# MCU.net
KiCad netlist of a schematic drawn in Altium Designer
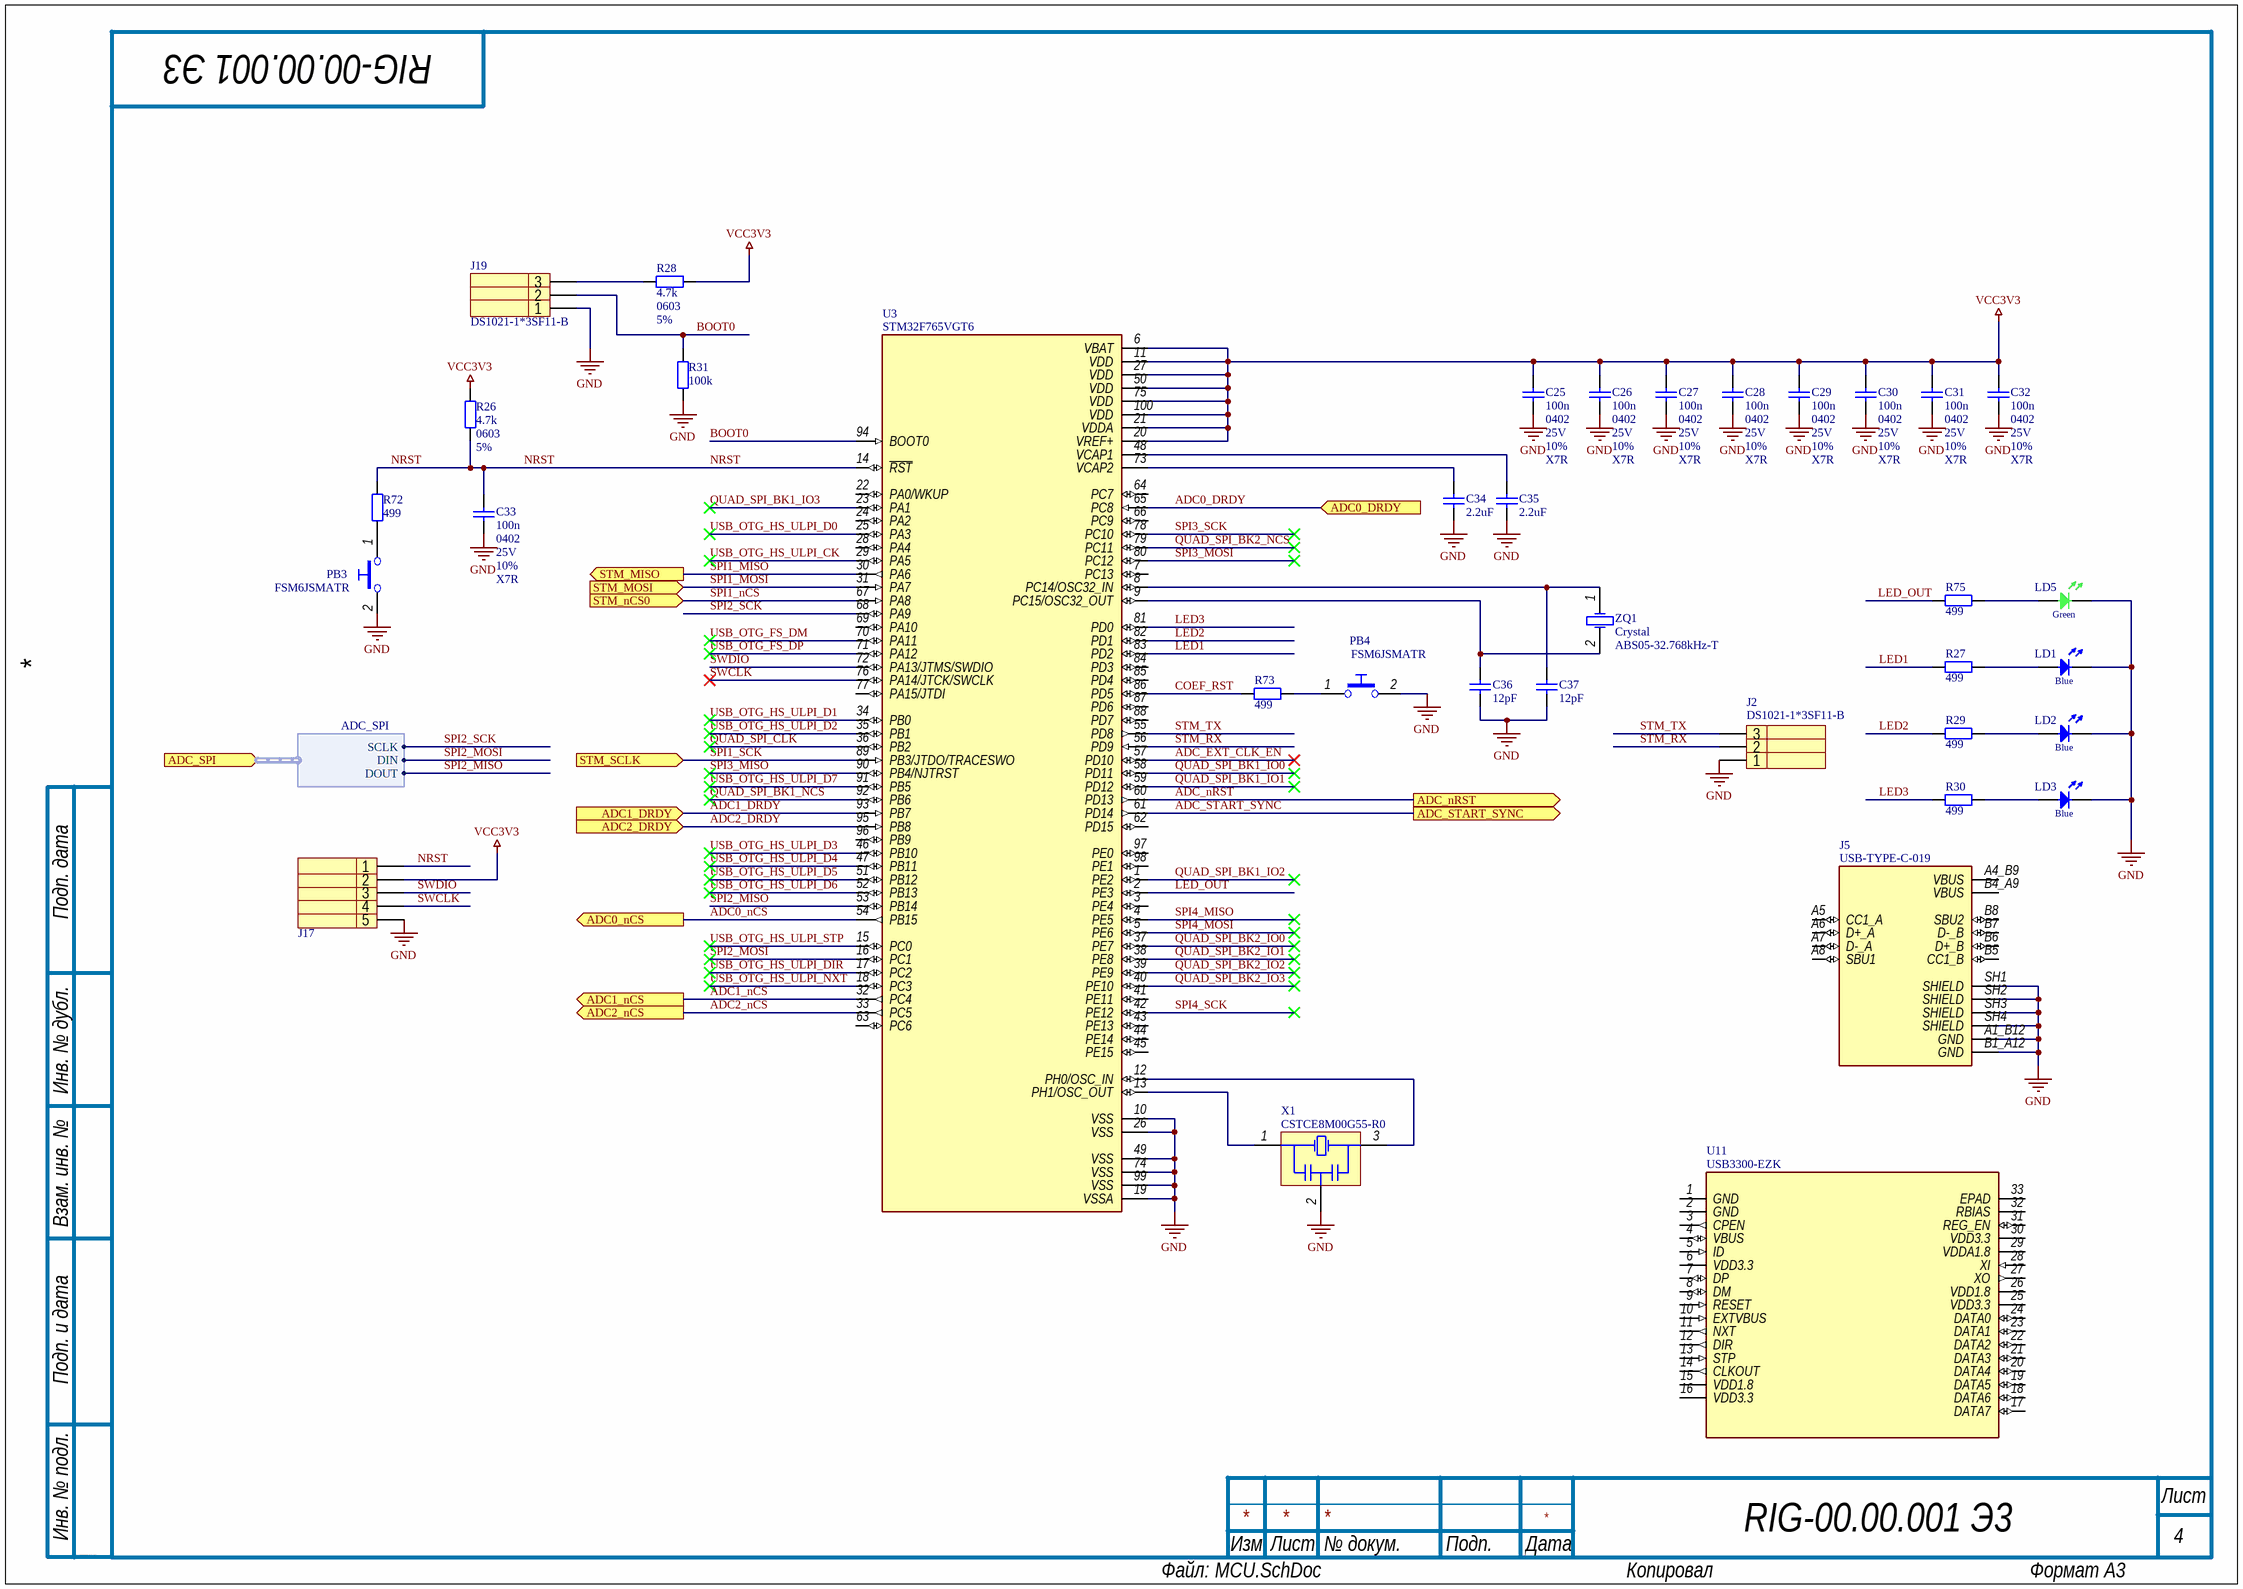
[diagram p0: MCU.SchDoc]

(export (version "E")
  (design (tool "Eeschema 10.0.6"))
  (components
    (comp (ref "C25")
      (value "100n")
      (footprint "CAPC1005X55N")
      (description "CAP CER 0402 100n 25V X7R")
      (fields
        (field (name "PART NUMBER") "GRM155R71E104KE14D")
        (field (name "DEVICE") "0402")
        (field (name "VOLTAGE") "25V")
        (field (name "TOLERANCE") "10%")
        (field (name "DIELECTRIC TYPE") "X7R")
        (field (name "MANUFACTURER") "Murata")
        (field (name "AUTHOR") "Krepak V.")
      )
      (libsource (lib "tgl_lib_altium") (part "Capacitor - non polarized"))
    )
    (comp (ref "C26")
      (value "100n")
      (footprint "CAPC1005X55N")
      (description "CAP CER 0402 100n 25V X7R")
      (fields
        (field (name "PART NUMBER") "GRM155R71E104KE14D")
        (field (name "DEVICE") "0402")
        (field (name "VOLTAGE") "25V")
        (field (name "TOLERANCE") "10%")
        (field (name "DIELECTRIC TYPE") "X7R")
        (field (name "MANUFACTURER") "Murata")
        (field (name "AUTHOR") "Krepak V.")
      )
      (libsource (lib "tgl_lib_altium") (part "Capacitor - non polarized"))
    )
    (comp (ref "C27")
      (value "100n")
      (footprint "CAPC1005X55N")
      (description "CAP CER 0402 100n 25V X7R")
      (fields
        (field (name "PART NUMBER") "GRM155R71E104KE14D")
        (field (name "DEVICE") "0402")
        (field (name "VOLTAGE") "25V")
        (field (name "TOLERANCE") "10%")
        (field (name "DIELECTRIC TYPE") "X7R")
        (field (name "MANUFACTURER") "Murata")
        (field (name "AUTHOR") "Krepak V.")
      )
      (libsource (lib "tgl_lib_altium") (part "Capacitor - non polarized"))
    )
    (comp (ref "C28")
      (value "100n")
      (footprint "CAPC1005X55N")
      (description "CAP CER 0402 100n 25V X7R")
      (fields
        (field (name "PART NUMBER") "GRM155R71E104KE14D")
        (field (name "DEVICE") "0402")
        (field (name "VOLTAGE") "25V")
        (field (name "TOLERANCE") "10%")
        (field (name "DIELECTRIC TYPE") "X7R")
        (field (name "MANUFACTURER") "Murata")
        (field (name "AUTHOR") "Krepak V.")
      )
      (libsource (lib "tgl_lib_altium") (part "Capacitor - non polarized"))
    )
    (comp (ref "C29")
      (value "100n")
      (footprint "CAPC1005X55N")
      (description "CAP CER 0402 100n 25V X7R")
      (fields
        (field (name "PART NUMBER") "GRM155R71E104KE14D")
        (field (name "DEVICE") "0402")
        (field (name "VOLTAGE") "25V")
        (field (name "TOLERANCE") "10%")
        (field (name "DIELECTRIC TYPE") "X7R")
        (field (name "MANUFACTURER") "Murata")
        (field (name "AUTHOR") "Krepak V.")
      )
      (libsource (lib "tgl_lib_altium") (part "Capacitor - non polarized"))
    )
    (comp (ref "C30")
      (value "100n")
      (footprint "CAPC1005X55N")
      (description "CAP CER 0402 100n 25V X7R")
      (fields
        (field (name "PART NUMBER") "GRM155R71E104KE14D")
        (field (name "DEVICE") "0402")
        (field (name "VOLTAGE") "25V")
        (field (name "TOLERANCE") "10%")
        (field (name "DIELECTRIC TYPE") "X7R")
        (field (name "MANUFACTURER") "Murata")
        (field (name "AUTHOR") "Krepak V.")
      )
      (libsource (lib "tgl_lib_altium") (part "Capacitor - non polarized"))
    )
    (comp (ref "C31")
      (value "100n")
      (footprint "CAPC1005X55N")
      (description "CAP CER 0402 100n 25V X7R")
      (fields
        (field (name "PART NUMBER") "GRM155R71E104KE14D")
        (field (name "DEVICE") "0402")
        (field (name "VOLTAGE") "25V")
        (field (name "TOLERANCE") "10%")
        (field (name "DIELECTRIC TYPE") "X7R")
        (field (name "MANUFACTURER") "Murata")
        (field (name "AUTHOR") "Krepak V.")
      )
      (libsource (lib "tgl_lib_altium") (part "Capacitor - non polarized"))
    )
    (comp (ref "C32")
      (value "100n")
      (footprint "CAPC1005X55N")
      (description "CAP CER 0402 100n 25V X7R")
      (fields
        (field (name "PART NUMBER") "GRM155R71E104KE14D")
        (field (name "DEVICE") "0402")
        (field (name "VOLTAGE") "25V")
        (field (name "TOLERANCE") "10%")
        (field (name "DIELECTRIC TYPE") "X7R")
        (field (name "MANUFACTURER") "Murata")
        (field (name "AUTHOR") "Krepak V.")
      )
      (libsource (lib "tgl_lib_altium") (part "Capacitor - non polarized"))
    )
    (comp (ref "C33")
      (value "100n")
      (footprint "CAPC1005X55N")
      (description "CAP CER 0402 100n 25V X7R")
      (fields
        (field (name "PART NUMBER") "GRM155R71E104KE14D")
        (field (name "DEVICE") "0402")
        (field (name "VOLTAGE") "25V")
        (field (name "TOLERANCE") "10%")
        (field (name "DIELECTRIC TYPE") "X7R")
        (field (name "MANUFACTURER") "Murata")
        (field (name "AUTHOR") "Krepak V.")
      )
      (libsource (lib "tgl_lib_altium") (part "Capacitor - non polarized"))
    )
    (comp (ref "C34")
      (value "2.2uF")
      (footprint "CAPC1005X55N")
      (description "CAP CER 0402 2.2uF 10V X5R")
      (fields
        (field (name "PART NUMBER") "GRM155R61A225KE95D")
        (field (name "VOLTAGE") "10V")
        (field (name "AUTHOR") "Krepak V.")
      )
      (libsource (lib "tgl_lib_altium") (part "Capacitor - non polarized"))
    )
    (comp (ref "C35")
      (value "2.2uF")
      (footprint "CAPC1005X55N")
      (description "CAP CER 0402 2.2uF 10V X5R")
      (fields
        (field (name "PART NUMBER") "GRM155R61A225KE95D")
        (field (name "VOLTAGE") "10V")
        (field (name "AUTHOR") "Krepak V.")
      )
      (libsource (lib "tgl_lib_altium") (part "Capacitor - non polarized"))
    )
    (comp (ref "C36")
      (value "12pF")
      (footprint "CAPC1005X55N")
      (description "CAP CER 0402 12pF 50V NP0")
      (fields
        (field (name "PART NUMBER") "GRM1555C1H120JA01D")
        (field (name "VOLTAGE") "50V")
        (field (name "AUTHOR") "Krepak V.")
      )
      (libsource (lib "tgl_lib_altium") (part "Capacitor - non polarized"))
    )
    (comp (ref "C37")
      (value "12pF")
      (footprint "CAPC1005X55N")
      (description "CAP CER 0402 12pF 50V NP0")
      (fields
        (field (name "PART NUMBER") "GRM1555C1H120JA01D")
        (field (name "VOLTAGE") "50V")
        (field (name "AUTHOR") "Krepak V.")
      )
      (libsource (lib "tgl_lib_altium") (part "Capacitor - non polarized"))
    )
    (comp (ref "J2")
      (value "DS1021-1*3SF11-B")
      (footprint "PLS-3")
      (fields (field (name "MANUFACTURER") "CONNFLY") (field (name "AUTHOR") "Arshanitsa D."))
      (libsource (lib "") (part "PLS-3_1"))
    )
    (comp (ref "J5")
      (value "USB-TYPE-C-019")
      (footprint "AMPHENOL_12402012E212A")
      (description "1 16P -25℃~+85℃ Type-C SMD USB, DVI, HDMI Connector Assemblies RoHS")
      (fields (field (name "MP") "12402012E212A") (field (name "MF") "Amphenol ICC (Commercial Products)"))
      (libsource (lib "tgl_lib_altium") (part "12402012E212A"))
    )
    (comp (ref "J17")
      (value "DS1021-1*5SF11-B")
      (footprint "PLS-5")
      (fields (field (name "MANUFACTURER") "CONNFLY") (field (name "AUTHOR") "Arshanitsa D."))
      (libsource (lib "tgl_lib_altium") (part "PLS-5"))
    )
    (comp (ref "J19")
      (value "DS1021-1*3SF11-B")
      (footprint "PLS-3")
      (fields (field (name "MANUFACTURER") "CONNFLY") (field (name "AUTHOR") "Arshanitsa D."))
      (libsource (lib "tgl_lib_altium") (part "PLS-3"))
    )
    (comp (ref "LD1")
      (value "Blue")
      (footprint "0603(LED_B)")
      (description "DIODE LTST-C191TBKT-5A")
      (fields (field (name "PART NUMBER") "LTST-C191TBKT-5A") (field (name "AUTHOR") "Krepak V."))
      (libsource (lib "tgl_lib_altium") (part "LED Blue 1A 2C"))
    )
    (comp (ref "LD2")
      (value "Blue")
      (footprint "0603(LED_B)")
      (description "DIODE LTST-C191TBKT-5A")
      (fields (field (name "PART NUMBER") "LTST-C191TBKT-5A") (field (name "AUTHOR") "Krepak V."))
      (libsource (lib "tgl_lib_altium") (part "LED Blue 1A 2C"))
    )
    (comp (ref "LD3")
      (value "Blue")
      (footprint "0603(LED_B)")
      (description "DIODE LTST-C191TBKT-5A")
      (fields (field (name "PART NUMBER") "LTST-C191TBKT-5A") (field (name "AUTHOR") "Krepak V."))
      (libsource (lib "tgl_lib_altium") (part "LED Blue 1A 2C"))
    )
    (comp (ref "LD5")
      (value "Green")
      (footprint "LD-3mm-G")
      (description "DIODE GREEN")
      (fields
        (field (name "PART NUMBER") "GNL-3012GD")
        (field (name "MANUFACTURER") "G-NOR OPTOELECTRONICS")
        (field (name "AUTHOR") "Krepak V.")
      )
      (libsource (lib "tgl_lib_altium") (part "LED Green 1A 2C"))
    )
    (comp (ref "PB3")
      (value "FSM6JSMATR")
      (footprint "FSMxJSMA-Series")
      (description "Tactile Switch SPST-NO Top Actuated Surface Mount")
      (fields (field (name "MANUFACTURER") "Te Connectivity") (field (name "AUTHOR") "Krepak V."))
      (libsource (lib "") (part "PB SPST 12NO_1"))
    )
    (comp (ref "PB4")
      (value "FSM6JSMATR")
      (footprint "FSMxJSMA-Series")
      (description "Tactile Switch SPST-NO Top Actuated Surface Mount")
      (fields (field (name "MANUFACTURER") "Te Connectivity") (field (name "AUTHOR") "Krepak V."))
      (libsource (lib "tgl_lib_altium") (part "PB SPST 12NO"))
    )
    (comp (ref "R26")
      (value "4.7k")
      (footprint "RESC1608X50N")
      (description "RES 0603 4.7k 5%")
      (fields
        (field (name "PART NUMBER") "RC0603JR-074K7L")
        (field (name "DEVICE") "0603")
        (field (name "TOLERANCE") "5%")
        (field (name "MANUFACTURER") "Yageo")
        (field (name "AUTHOR") "Krepak V.")
      )
      (libsource (lib "") (part "Resistor1_1"))
    )
    (comp (ref "R27")
      (value "499")
      (footprint "RESC1005X40N")
      (description "RES 0402 499 1%")
      (fields
        (field (name "PART NUMBER") "RC0402FR-07499RL")
        (field (name "TOLERANCE") "1%")
        (field (name "AUTHOR") "Krepak V.")
      )
      (libsource (lib "tgl_lib_altium") (part "Resistor1"))
    )
    (comp (ref "R28")
      (value "4.7k")
      (footprint "RESC1608X50N")
      (description "RES 0603 4.7k 5%")
      (fields
        (field (name "PART NUMBER") "RC0603JR-074K7L")
        (field (name "DEVICE") "0603")
        (field (name "TOLERANCE") "5%")
        (field (name "MANUFACTURER") "Yageo")
        (field (name "AUTHOR") "Krepak V.")
      )
      (libsource (lib "tgl_lib_altium") (part "Resistor1"))
    )
    (comp (ref "R29")
      (value "499")
      (footprint "RESC1005X40N")
      (description "RES 0402 499 1%")
      (fields
        (field (name "PART NUMBER") "RC0402FR-07499RL")
        (field (name "TOLERANCE") "1%")
        (field (name "AUTHOR") "Krepak V.")
      )
      (libsource (lib "tgl_lib_altium") (part "Resistor1"))
    )
    (comp (ref "R30")
      (value "499")
      (footprint "RESC1005X40N")
      (description "RES 0402 499 1%")
      (fields
        (field (name "PART NUMBER") "RC0402FR-07499RL")
        (field (name "TOLERANCE") "1%")
        (field (name "AUTHOR") "Krepak V.")
      )
      (libsource (lib "tgl_lib_altium") (part "Resistor1"))
    )
    (comp (ref "R31")
      (value "100k")
      (footprint "RESC1005X40N")
      (description "RES 0402 100k 1%")
      (fields
        (field (name "PART NUMBER") "RC0402FR-07100KL")
        (field (name "TOLERANCE") "1%")
        (field (name "AUTHOR") "Krepak V.")
      )
      (libsource (lib "tgl_lib_altium") (part "Resistor1"))
    )
    (comp (ref "R72")
      (value "499")
      (footprint "RESC1005X40N")
      (description "RES 0402 499 1%")
      (fields
        (field (name "PART NUMBER") "RC0402FR-07499RL")
        (field (name "TOLERANCE") "1%")
        (field (name "AUTHOR") "Krepak V.")
      )
      (libsource (lib "tgl_lib_altium") (part "Resistor1"))
    )
    (comp (ref "R73")
      (value "499")
      (footprint "RESC1005X40N")
      (description "RES 0402 499 1%")
      (fields
        (field (name "PART NUMBER") "RC0402FR-07499RL")
        (field (name "TOLERANCE") "1%")
        (field (name "AUTHOR") "Krepak V.")
      )
      (libsource (lib "") (part "Resistor1_2"))
    )
    (comp (ref "R75")
      (value "499")
      (footprint "RESC1005X40N")
      (description "RES 0402 499 1%")
      (fields
        (field (name "PART NUMBER") "RC0402FR-07499RL")
        (field (name "TOLERANCE") "1%")
        (field (name "AUTHOR") "Krepak V.")
      )
      (libsource (lib "tgl_lib_altium") (part "Resistor1"))
    )
    (comp (ref "U3")
      (value "STM32F765VGT6")
      (footprint "LQFP100_L")
      (fields
        (field (name "MF") "STMicroelectronics")
        (field (name "MP") "STM32F765VGT6TR")
        (field (name "MANUFACTURER") "ST Microelectronics")
        (field (name "AUTHOR") "Krepak V.")
      )
      (libsource (lib "tgl_lib_altium") (part "STM32F765VGT6"))
    )
    (comp (ref "U11")
      (value "USB3300-EZK")
      (footprint "QFN32_5X5MC_MCH")
      (description "USB Controller USB 2.0, OTG ULPI Interface 32-QFN (5x5)")
      (fields
        (field (name "MANUFACTURER") "Microchip Technology")
        (field (name "COPYRIGHT") "Copyright (C) 2025 Ultra Librarian. All rights reserved.")
        (field (name "AUTHOR") "Krepak V.")
      )
      (libsource (lib "tgl_lib_altium") (part "USB3300-EZK"))
    )
    (comp (ref "X1")
      (value "CSTCE8M00G55-R0")
      (footprint "MURA-CSTCE_G_A-3_V")
      (description "8MHz ±0.5% 33pF SMD3213-3P Ceramic Resonators ROHS")
      (fields
        (field (name "TOLERANCE") "0.5%")
        (field (name "MANUFACTURER") "Murata")
        (field (name "AUTHOR") "Krepak V.")
      )
      (libsource (lib "tgl_lib_altium") (part "Crystal_1"))
    )
    (comp (ref "ZQ1")
      (value "Crystal")
      (footprint "FP-ABS05-MFG")
      (description "32.768kHz 12.5pF ±20ppm SMD1610-2P Crystals ROHS")
      (fields
        (field (name "PART NUMBER") "ABS05-32.768kHz-T")
        (field (name "MANUFACTURER") "Abracon")
        (field (name "MANUFACTURER PART NUMBER") "ABS05-32.768kHz-T")
        (field (name "AUTHOR") "Krepak V.")
      )
      (libsource (lib "tgl_lib_altium") (part "Crystal"))
    )
  )
  (nets
    (net (code "2") (name "/ADC0_DRDY") (class "Default")
      (node (ref "U3") (pin "65") (pinfunction "PC8_65") (pintype "input"))
    )
    (net (code "3") (name "/ADC0_nCS") (class "Default")
      (node (ref "U3") (pin "54") (pinfunction "PB15_54") (pintype "output"))
    )
    (net (code "4") (name "/ADC1_DRDY") (class "Default")
      (node (ref "U3") (pin "93") (pinfunction "PB7_93") (pintype "input"))
    )
    (net (code "5") (name "/ADC1_nCS") (class "Default")
      (node (ref "U3") (pin "32") (pinfunction "PC4_32") (pintype "output"))
    )
    (net (code "6") (name "/ADC2_DRDY") (class "Default")
      (node (ref "U3") (pin "95") (pinfunction "PB8_95") (pintype "input"))
    )
    (net (code "7") (name "/ADC2_nCS") (class "Default")
      (node (ref "U3") (pin "33") (pinfunction "PC5_33") (pintype "output"))
    )
    (net (code "8") (name "/ADC_EXT_CLK_EN") (class "Default")
      (node (ref "U3") (pin "57") (pinfunction "PD10_57") (pintype "bidirectional+no_connect"))
    )
    (net (code "9") (name "/ADC_START_SYNC") (class "Default")
      (node (ref "U3") (pin "61") (pinfunction "PD14_61") (pintype "output"))
    )
    (net (code "10") (name "/ADC_nRST") (class "Default")
      (node (ref "U3") (pin "60") (pinfunction "PD13_60") (pintype "output"))
    )
    (net (code "11") (name "/BOOT0") (class "Default")
      (node (ref "J19") (pin "2") (pinfunction "2_2") (pintype "power_in"))
      (node (ref "R31") (pin "2") (pinfunction "2_2") (pintype "passive"))
      (node (ref "U3") (pin "94") (pinfunction "BOOT0_94") (pintype "input"))
    )
    (net (code "12") (name "/COEF_RST") (class "Default")
      (node (ref "R73") (pin "2") (pinfunction "2_2") (pintype "passive"))
      (node (ref "U3") (pin "86") (pinfunction "PD5_86") (pintype "bidirectional"))
    )
    (net (code "13") (name "/LED1") (class "Default")
      (node (ref "R27") (pin "1") (pinfunction "1_1") (pintype "passive"))
      (node (ref "U3") (pin "83") (pinfunction "PD2_83") (pintype "bidirectional"))
    )
    (net (code "14") (name "/LED2") (class "Default")
      (node (ref "R29") (pin "1") (pinfunction "1_1") (pintype "passive"))
      (node (ref "U3") (pin "82") (pinfunction "PD1_82") (pintype "bidirectional"))
    )
    (net (code "15") (name "/LED3") (class "Default")
      (node (ref "R30") (pin "1") (pinfunction "1_1") (pintype "passive"))
      (node (ref "U3") (pin "81") (pinfunction "PD0_81") (pintype "bidirectional"))
    )
    (net (code "16") (name "/LED_OUT") (class "Default")
      (node (ref "R75") (pin "1") (pinfunction "1_1") (pintype "passive"))
      (node (ref "U3") (pin "2") (pinfunction "PE3_2") (pintype "bidirectional"))
    )
    (net (code "17") (name "/NRST") (class "Default")
      (node (ref "C33") (pin "2") (pinfunction "2_2") (pintype "passive"))
      (node (ref "J17") (pin "1") (pinfunction "1_1") (pintype "passive"))
      (node (ref "R26") (pin "1") (pinfunction "1_1") (pintype "passive"))
      (node (ref "R72") (pin "2") (pinfunction "2_2") (pintype "passive"))
      (node (ref "U3") (pin "14") (pinfunction "~{RST}_14") (pintype "bidirectional"))
    )
    (net (code "18") (name "/QUAD_SPI_BK1_IO0") (class "Default")
      (node (ref "U3") (pin "58") (pinfunction "PD11_58") (pintype "bidirectional+no_connect"))
    )
    (net (code "19") (name "/QUAD_SPI_BK1_IO1") (class "Default")
      (node (ref "U3") (pin "59") (pinfunction "PD12_59") (pintype "bidirectional+no_connect"))
    )
    (net (code "20") (name "/QUAD_SPI_BK1_IO2") (class "Default")
      (node (ref "U3") (pin "1") (pinfunction "PE2_1") (pintype "bidirectional+no_connect"))
    )
    (net (code "21") (name "/QUAD_SPI_BK1_IO3") (class "Default")
      (node (ref "U3") (pin "23") (pinfunction "PA1_23") (pintype "bidirectional+no_connect"))
    )
    (net (code "22") (name "/QUAD_SPI_BK1_NCS") (class "Default")
      (node (ref "U3") (pin "92") (pinfunction "PB6_92") (pintype "bidirectional+no_connect"))
    )
    (net (code "23") (name "/QUAD_SPI_BK2_IO0") (class "Default")
      (node (ref "U3") (pin "37") (pinfunction "PE7_37") (pintype "bidirectional+no_connect"))
    )
    (net (code "24") (name "/QUAD_SPI_BK2_IO1") (class "Default")
      (node (ref "U3") (pin "38") (pinfunction "PE8_38") (pintype "bidirectional+no_connect"))
    )
    (net (code "25") (name "/QUAD_SPI_BK2_IO2") (class "Default")
      (node (ref "U3") (pin "39") (pinfunction "PE9_39") (pintype "bidirectional+no_connect"))
    )
    (net (code "26") (name "/QUAD_SPI_BK2_IO3") (class "Default")
      (node (ref "U3") (pin "40") (pinfunction "PE10_40") (pintype "bidirectional+no_connect"))
    )
    (net (code "27") (name "/QUAD_SPI_BK2_NCS") (class "Default")
      (node (ref "U3") (pin "79") (pinfunction "PC11_79") (pintype "bidirectional+no_connect"))
    )
    (net (code "28") (name "/QUAD_SPI_CLK") (class "Default")
      (node (ref "U3") (pin "36") (pinfunction "PB2_36") (pintype "bidirectional+no_connect"))
    )
    (net (code "29") (name "/SPI1_MISO") (class "Default")
      (node (ref "U3") (pin "30") (pinfunction "PA6_30") (pintype "output"))
    )
    (net (code "30") (name "/SPI1_MOSI") (class "Default")
      (node (ref "U3") (pin "31") (pinfunction "PA7_31") (pintype "input"))
    )
    (net (code "31") (name "/SPI1_SCK") (class "Default")
      (node (ref "U3") (pin "89") (pinfunction "PB3/JTDO/TRACESWO_89") (pintype "input"))
    )
    (net (code "32") (name "/SPI1_nCS") (class "Default")
      (node (ref "U3") (pin "67") (pinfunction "PA8_67") (pintype "input"))
    )
    (net (code "33") (name "/SPI2_MISO") (class "Default")
      (node (ref "U3") (pin "53") (pinfunction "PB14_53") (pintype "bidirectional"))
    )
    (net (code "34") (name "/SPI2_MOSI") (class "Default")
      (node (ref "U3") (pin "16") (pinfunction "PC1_16") (pintype "bidirectional"))
    )
    (net (code "35") (name "/SPI2_SCK") (class "Default")
      (node (ref "U3") (pin "68") (pinfunction "PA9_68") (pintype "bidirectional"))
    )
    (net (code "36") (name "/SPI3_MISO") (class "Default")
      (node (ref "U3") (pin "90") (pinfunction "PB4/NJTRST_90") (pintype "bidirectional+no_connect"))
    )
    (net (code "37") (name "/SPI3_MOSI") (class "Default")
      (node (ref "U3") (pin "80") (pinfunction "PC12_80") (pintype "bidirectional+no_connect"))
    )
    (net (code "38") (name "/SPI3_SCK") (class "Default")
      (node (ref "U3") (pin "78") (pinfunction "PC10_78") (pintype "bidirectional+no_connect"))
    )
    (net (code "39") (name "/SPI4_MISO") (class "Default")
      (node (ref "U3") (pin "4") (pinfunction "PE5_4") (pintype "bidirectional+no_connect"))
    )
    (net (code "40") (name "/SPI4_MOSI") (class "Default")
      (node (ref "U3") (pin "5") (pinfunction "PE6_5") (pintype "bidirectional+no_connect"))
    )
    (net (code "41") (name "/SPI4_SCK") (class "Default")
      (node (ref "U3") (pin "42") (pinfunction "PE12_42") (pintype "bidirectional+no_connect"))
    )
    (net (code "42") (name "/STM_RX") (class "Default")
      (node (ref "J2") (pin "2") (pinfunction "2_2") (pintype "power_in"))
      (node (ref "U3") (pin "56") (pinfunction "PD9_56") (pintype "input"))
    )
    (net (code "43") (name "/STM_TX") (class "Default")
      (node (ref "J2") (pin "3") (pinfunction "3_3") (pintype "passive"))
      (node (ref "U3") (pin "55") (pinfunction "PD8_55") (pintype "output"))
    )
    (net (code "44") (name "/SWCLK") (class "Default")
      (node (ref "J17") (pin "4") (pinfunction "4_4") (pintype "power_in"))
      (node (ref "U3") (pin "76") (pinfunction "PA14/JTCK/SWCLK_76") (pintype "bidirectional"))
    )
    (net (code "45") (name "/SWDIO") (class "Default")
      (node (ref "J17") (pin "3") (pinfunction "3_3") (pintype "passive"))
      (node (ref "U3") (pin "72") (pinfunction "PA13/JTMS/SWDIO_72") (pintype "bidirectional"))
    )
    (net (code "46") (name "/USB_OTG_FS_DM") (class "Default")
      (node (ref "U3") (pin "70") (pinfunction "PA11_70") (pintype "bidirectional+no_connect"))
    )
    (net (code "47") (name "/USB_OTG_FS_DP") (class "Default")
      (node (ref "U3") (pin "71") (pinfunction "PA12_71") (pintype "bidirectional+no_connect"))
    )
    (net (code "48") (name "/USB_OTG_HS_ULPI_CK") (class "Default")
      (node (ref "U3") (pin "29") (pinfunction "PA5_29") (pintype "bidirectional+no_connect"))
    )
    (net (code "49") (name "/USB_OTG_HS_ULPI_D0") (class "Default")
      (node (ref "U3") (pin "25") (pinfunction "PA3_25") (pintype "bidirectional+no_connect"))
    )
    (net (code "50") (name "/USB_OTG_HS_ULPI_D1") (class "Default")
      (node (ref "U3") (pin "34") (pinfunction "PB0_34") (pintype "bidirectional+no_connect"))
    )
    (net (code "51") (name "/USB_OTG_HS_ULPI_D2") (class "Default")
      (node (ref "U3") (pin "35") (pinfunction "PB1_35") (pintype "bidirectional+no_connect"))
    )
    (net (code "52") (name "/USB_OTG_HS_ULPI_D3") (class "Default")
      (node (ref "U3") (pin "46") (pinfunction "PB10_46") (pintype "bidirectional+no_connect"))
    )
    (net (code "53") (name "/USB_OTG_HS_ULPI_D4") (class "Default")
      (node (ref "U3") (pin "47") (pinfunction "PB11_47") (pintype "bidirectional+no_connect"))
    )
    (net (code "54") (name "/USB_OTG_HS_ULPI_D5") (class "Default")
      (node (ref "U3") (pin "51") (pinfunction "PB12_51") (pintype "bidirectional+no_connect"))
    )
    (net (code "55") (name "/USB_OTG_HS_ULPI_D6") (class "Default")
      (node (ref "U3") (pin "52") (pinfunction "PB13_52") (pintype "bidirectional+no_connect"))
    )
    (net (code "56") (name "/USB_OTG_HS_ULPI_D7") (class "Default")
      (node (ref "U3") (pin "91") (pinfunction "PB5_91") (pintype "bidirectional+no_connect"))
    )
    (net (code "57") (name "/USB_OTG_HS_ULPI_DIR") (class "Default")
      (node (ref "U3") (pin "17") (pinfunction "PC2_17") (pintype "bidirectional+no_connect"))
    )
    (net (code "58") (name "/USB_OTG_HS_ULPI_NXT") (class "Default")
      (node (ref "U3") (pin "18") (pinfunction "PC3_18") (pintype "bidirectional+no_connect"))
    )
    (net (code "59") (name "/USB_OTG_HS_ULPI_STP") (class "Default")
      (node (ref "U3") (pin "15") (pinfunction "PC0_15") (pintype "bidirectional+no_connect"))
    )
    (net (code "61") (name "GND") (class "Default")
      (node (ref "C25") (pin "1") (pinfunction "1_1") (pintype "passive"))
      (node (ref "C26") (pin "1") (pinfunction "1_1") (pintype "passive"))
      (node (ref "C27") (pin "1") (pinfunction "1_1") (pintype "passive"))
      (node (ref "C28") (pin "1") (pinfunction "1_1") (pintype "passive"))
      (node (ref "C29") (pin "1") (pinfunction "1_1") (pintype "passive"))
      (node (ref "C30") (pin "1") (pinfunction "1_1") (pintype "passive"))
      (node (ref "C31") (pin "1") (pinfunction "1_1") (pintype "passive"))
      (node (ref "C32") (pin "1") (pinfunction "1_1") (pintype "passive"))
      (node (ref "C33") (pin "1") (pinfunction "1_1") (pintype "passive"))
      (node (ref "C34") (pin "1") (pinfunction "1_1") (pintype "passive"))
      (node (ref "C35") (pin "1") (pinfunction "1_1") (pintype "passive"))
      (node (ref "C36") (pin "1") (pinfunction "1_1") (pintype "passive"))
      (node (ref "C37") (pin "1") (pinfunction "1_1") (pintype "passive"))
      (node (ref "J17") (pin "5") (pinfunction "5_5") (pintype "passive"))
      (node (ref "J19") (pin "1") (pinfunction "1_1") (pintype "passive"))
      (node (ref "J2") (pin "1") (pinfunction "1_1") (pintype "passive"))
      (node (ref "J5") (pin "A1_B12") (pinfunction "GND_A1_B12") (pintype "power_in"))
      (node (ref "J5") (pin "B1_A12") (pinfunction "GND_B1_A12") (pintype "power_in"))
      (node (ref "J5") (pin "SH1") (pinfunction "SHIELD_SH1") (pintype "passive"))
      (node (ref "J5") (pin "SH2") (pinfunction "SHIELD_SH2") (pintype "passive"))
      (node (ref "J5") (pin "SH3") (pinfunction "SHIELD_SH3") (pintype "passive"))
      (node (ref "J5") (pin "SH4") (pinfunction "SHIELD_SH4") (pintype "passive"))
      (node (ref "LD1") (pin "2") (pinfunction "C_2") (pintype "passive"))
      (node (ref "LD2") (pin "2") (pinfunction "C_2") (pintype "passive"))
      (node (ref "LD3") (pin "2") (pinfunction "C_2") (pintype "passive"))
      (node (ref "LD5") (pin "2") (pinfunction "C_2") (pintype "passive"))
      (node (ref "PB3") (pin "2") (pinfunction "2_2") (pintype "passive"))
      (node (ref "PB4") (pin "2") (pinfunction "2_2") (pintype "passive"))
      (node (ref "R31") (pin "1") (pinfunction "1_1") (pintype "passive"))
      (node (ref "U3") (pin "10") (pinfunction "VSS_10") (pintype "power_in"))
      (node (ref "U3") (pin "19") (pinfunction "VSSA_19") (pintype "power_in"))
      (node (ref "U3") (pin "26") (pinfunction "VSS_26") (pintype "power_in"))
      (node (ref "U3") (pin "49") (pinfunction "VSS_49") (pintype "power_in"))
      (node (ref "U3") (pin "74") (pinfunction "VSS_74") (pintype "power_in"))
      (node (ref "U3") (pin "99") (pinfunction "VSS_99") (pintype "power_in"))
      (node (ref "X1") (pin "2") (pinfunction "GND_2") (pintype "power_in"))
    )
    (net (code "62") (name "Net-(J19-Pad3)") (class "Default")
      (node (ref "J19") (pin "3") (pinfunction "3_3") (pintype "passive"))
      (node (ref "R28") (pin "1") (pinfunction "1_1") (pintype "passive"))
    )
    (net (code "63") (name "Net-(LD1-A)") (class "Default")
      (node (ref "LD1") (pin "1") (pinfunction "A_1") (pintype "passive"))
      (node (ref "R27") (pin "2") (pinfunction "2_2") (pintype "passive"))
    )
    (net (code "64") (name "Net-(LD2-A)") (class "Default")
      (node (ref "LD2") (pin "1") (pinfunction "A_1") (pintype "passive"))
      (node (ref "R29") (pin "2") (pinfunction "2_2") (pintype "passive"))
    )
    (net (code "65") (name "Net-(LD3-A)") (class "Default")
      (node (ref "LD3") (pin "1") (pinfunction "A_1") (pintype "passive"))
      (node (ref "R30") (pin "2") (pinfunction "2_2") (pintype "passive"))
    )
    (net (code "66") (name "Net-(LD5-A)") (class "Default")
      (node (ref "LD5") (pin "1") (pinfunction "A_1") (pintype "passive"))
      (node (ref "R75") (pin "2") (pinfunction "2_2") (pintype "passive"))
    )
    (net (code "67") (name "Net-(PB3-Pad1)") (class "Default")
      (node (ref "PB3") (pin "1") (pinfunction "1_1") (pintype "passive"))
      (node (ref "R72") (pin "1") (pinfunction "1_1") (pintype "passive"))
    )
    (net (code "68") (name "Net-(PB4-Pad1)") (class "Default")
      (node (ref "PB4") (pin "1") (pinfunction "1_1") (pintype "passive"))
      (node (ref "R73") (pin "1") (pinfunction "1_1") (pintype "passive"))
    )
    (net (code "69") (name "Net-(U3-PC14{slash}OSC32_IN)") (class "Default")
      (node (ref "C37") (pin "2") (pinfunction "2_2") (pintype "passive"))
      (node (ref "U3") (pin "8") (pinfunction "PC14/OSC32_IN_8") (pintype "bidirectional"))
      (node (ref "ZQ1") (pin "1") (pinfunction "OSC1_1") (pintype "passive"))
    )
    (net (code "70") (name "Net-(U3-PC15{slash}OSC32_OUT)") (class "Default")
      (node (ref "C36") (pin "2") (pinfunction "2_2") (pintype "passive"))
      (node (ref "U3") (pin "9") (pinfunction "PC15/OSC32_OUT_9") (pintype "bidirectional"))
      (node (ref "ZQ1") (pin "2") (pinfunction "OSC2_2") (pintype "passive"))
    )
    (net (code "71") (name "Net-(U3-PH0{slash}OSC_IN)") (class "Default")
      (node (ref "U3") (pin "12") (pinfunction "PH0/OSC_IN_12") (pintype "bidirectional"))
      (node (ref "X1") (pin "3") (pinfunction "X2_3") (pintype "passive"))
    )
    (net (code "72") (name "Net-(U3-PH1{slash}OSC_OUT)") (class "Default")
      (node (ref "U3") (pin "13") (pinfunction "PH1/OSC_OUT_13") (pintype "bidirectional"))
      (node (ref "X1") (pin "1") (pinfunction "X1_1") (pintype "passive"))
    )
    (net (code "73") (name "Net-(U3-VCAP1)") (class "Default")
      (node (ref "C35") (pin "2") (pinfunction "2_2") (pintype "passive"))
      (node (ref "U3") (pin "48") (pinfunction "VCAP1_48") (pintype "power_in"))
    )
    (net (code "74") (name "Net-(U3-VCAP2)") (class "Default")
      (node (ref "C34") (pin "2") (pinfunction "2_2") (pintype "passive"))
      (node (ref "U3") (pin "73") (pinfunction "VCAP2_73") (pintype "power_in"))
    )
    (net (code "75") (name "VCC3V3") (class "Default")
      (node (ref "C25") (pin "2") (pinfunction "2_2") (pintype "passive"))
      (node (ref "C26") (pin "2") (pinfunction "2_2") (pintype "passive"))
      (node (ref "C27") (pin "2") (pinfunction "2_2") (pintype "passive"))
      (node (ref "C28") (pin "2") (pinfunction "2_2") (pintype "passive"))
      (node (ref "C29") (pin "2") (pinfunction "2_2") (pintype "passive"))
      (node (ref "C30") (pin "2") (pinfunction "2_2") (pintype "passive"))
      (node (ref "C31") (pin "2") (pinfunction "2_2") (pintype "passive"))
      (node (ref "C32") (pin "2") (pinfunction "2_2") (pintype "passive"))
      (node (ref "J17") (pin "2") (pinfunction "2_2") (pintype "power_in"))
      (node (ref "R26") (pin "2") (pinfunction "2_2") (pintype "passive"))
      (node (ref "R28") (pin "2") (pinfunction "2_2") (pintype "passive"))
      (node (ref "U3") (pin "100") (pinfunction "VDD_100") (pintype "power_in"))
      (node (ref "U3") (pin "11") (pinfunction "VDD_11") (pintype "power_in"))
      (node (ref "U3") (pin "20") (pinfunction "VREF+_20") (pintype "power_in"))
      (node (ref "U3") (pin "21") (pinfunction "VDDA_21") (pintype "power_in"))
      (node (ref "U3") (pin "27") (pinfunction "VDD_27") (pintype "power_in"))
      (node (ref "U3") (pin "50") (pinfunction "VDD_50") (pintype "power_in"))
      (node (ref "U3") (pin "6") (pinfunction "VBAT_6") (pintype "power_in"))
      (node (ref "U3") (pin "75") (pinfunction "VDD_75") (pintype "power_in"))
    )
    (net (code "76") (name "unconnected-(J5-CC1_A-PadA5)") (class "Default")
      (node (ref "J5") (pin "A5") (pinfunction "CC1_A_A5") (pintype "bidirectional"))
    )
    (net (code "77") (name "unconnected-(J5-CC1_B-PadB5)") (class "Default")
      (node (ref "J5") (pin "B5") (pinfunction "CC1_B_B5") (pintype "bidirectional"))
    )
    (net (code "78") (name "unconnected-(J5-D+_A-PadA6)") (class "Default")
      (node (ref "J5") (pin "A6") (pinfunction "D+_A_A6") (pintype "bidirectional"))
    )
    (net (code "79") (name "unconnected-(J5-D+_B-PadB6)") (class "Default")
      (node (ref "J5") (pin "B6") (pinfunction "D+_B_B6") (pintype "bidirectional"))
    )
    (net (code "80") (name "unconnected-(J5-D-_A-PadA7)") (class "Default")
      (node (ref "J5") (pin "A7") (pinfunction "D-_A_A7") (pintype "bidirectional"))
    )
    (net (code "81") (name "unconnected-(J5-D-_B-PadB7)") (class "Default")
      (node (ref "J5") (pin "B7") (pinfunction "D-_B_B7") (pintype "bidirectional"))
    )
    (net (code "82") (name "unconnected-(J5-SBU1-PadA8)") (class "Default")
      (node (ref "J5") (pin "A8") (pinfunction "SBU1_A8") (pintype "bidirectional"))
    )
    (net (code "83") (name "unconnected-(J5-SBU2-PadB8)") (class "Default")
      (node (ref "J5") (pin "B8") (pinfunction "SBU2_B8") (pintype "bidirectional"))
    )
    (net (code "84") (name "unconnected-(J5-VBUS-PadA4_B9)") (class "Default")
      (node (ref "J5") (pin "A4_B9") (pinfunction "VBUS_A4_B9") (pintype "power_in"))
    )
    (net (code "85") (name "unconnected-(J5-VBUS-PadB4_A9)") (class "Default")
      (node (ref "J5") (pin "B4_A9") (pinfunction "VBUS_B4_A9") (pintype "power_in"))
    )
    (net (code "86") (name "unconnected-(U3-PA0{slash}WKUP-Pad22)") (class "Default")
      (node (ref "U3") (pin "22") (pinfunction "PA0/WKUP_22") (pintype "bidirectional"))
    )
    (net (code "87") (name "unconnected-(U3-PA2-Pad24)") (class "Default")
      (node (ref "U3") (pin "24") (pinfunction "PA2_24") (pintype "bidirectional"))
    )
    (net (code "88") (name "unconnected-(U3-PA4-Pad28)") (class "Default")
      (node (ref "U3") (pin "28") (pinfunction "PA4_28") (pintype "bidirectional"))
    )
    (net (code "89") (name "unconnected-(U3-PA10-Pad69)") (class "Default")
      (node (ref "U3") (pin "69") (pinfunction "PA10_69") (pintype "bidirectional"))
    )
    (net (code "90") (name "unconnected-(U3-PA15{slash}JTDI-Pad77)") (class "Default")
      (node (ref "U3") (pin "77") (pinfunction "PA15/JTDI_77") (pintype "bidirectional"))
    )
    (net (code "91") (name "unconnected-(U3-PB9-Pad96)") (class "Default")
      (node (ref "U3") (pin "96") (pinfunction "PB9_96") (pintype "bidirectional"))
    )
    (net (code "92") (name "unconnected-(U3-PC6-Pad63)") (class "Default")
      (node (ref "U3") (pin "63") (pinfunction "PC6_63") (pintype "bidirectional"))
    )
    (net (code "93") (name "unconnected-(U3-PC7-Pad64)") (class "Default")
      (node (ref "U3") (pin "64") (pinfunction "PC7_64") (pintype "bidirectional"))
    )
    (net (code "94") (name "unconnected-(U3-PC9-Pad66)") (class "Default")
      (node (ref "U3") (pin "66") (pinfunction "PC9_66") (pintype "bidirectional"))
    )
    (net (code "95") (name "unconnected-(U3-PC13-Pad7)") (class "Default")
      (node (ref "U3") (pin "7") (pinfunction "PC13_7") (pintype "bidirectional"))
    )
    (net (code "96") (name "unconnected-(U3-PD3-Pad84)") (class "Default")
      (node (ref "U3") (pin "84") (pinfunction "PD3_84") (pintype "bidirectional"))
    )
    (net (code "97") (name "unconnected-(U3-PD4-Pad85)") (class "Default")
      (node (ref "U3") (pin "85") (pinfunction "PD4_85") (pintype "bidirectional"))
    )
    (net (code "98") (name "unconnected-(U3-PD6-Pad87)") (class "Default")
      (node (ref "U3") (pin "87") (pinfunction "PD6_87") (pintype "bidirectional"))
    )
    (net (code "99") (name "unconnected-(U3-PD7-Pad88)") (class "Default")
      (node (ref "U3") (pin "88") (pinfunction "PD7_88") (pintype "bidirectional"))
    )
    (net (code "100") (name "unconnected-(U3-PD15-Pad62)") (class "Default")
      (node (ref "U3") (pin "62") (pinfunction "PD15_62") (pintype "bidirectional"))
    )
    (net (code "101") (name "unconnected-(U3-PE0-Pad97)") (class "Default")
      (node (ref "U3") (pin "97") (pinfunction "PE0_97") (pintype "bidirectional"))
    )
    (net (code "102") (name "unconnected-(U3-PE1-Pad98)") (class "Default")
      (node (ref "U3") (pin "98") (pinfunction "PE1_98") (pintype "bidirectional"))
    )
    (net (code "103") (name "unconnected-(U3-PE4-Pad3)") (class "Default")
      (node (ref "U3") (pin "3") (pinfunction "PE4_3") (pintype "bidirectional"))
    )
    (net (code "104") (name "unconnected-(U3-PE11-Pad41)") (class "Default")
      (node (ref "U3") (pin "41") (pinfunction "PE11_41") (pintype "bidirectional"))
    )
    (net (code "105") (name "unconnected-(U3-PE13-Pad43)") (class "Default")
      (node (ref "U3") (pin "43") (pinfunction "PE13_43") (pintype "bidirectional"))
    )
    (net (code "106") (name "unconnected-(U3-PE14-Pad44)") (class "Default")
      (node (ref "U3") (pin "44") (pinfunction "PE14_44") (pintype "bidirectional"))
    )
    (net (code "107") (name "unconnected-(U3-PE15-Pad45)") (class "Default")
      (node (ref "U3") (pin "45") (pinfunction "PE15_45") (pintype "bidirectional"))
    )
    (net (code "108") (name "unconnected-(U11-CLKOUT-Pad14)") (class "Default")
      (node (ref "U11") (pin "14") (pinfunction "CLKOUT_14") (pintype "output"))
    )
    (net (code "109") (name "unconnected-(U11-CPEN-Pad3)") (class "Default")
      (node (ref "U11") (pin "3") (pinfunction "CPEN_3") (pintype "output"))
    )
    (net (code "110") (name "unconnected-(U11-DATA0-Pad24)") (class "Default")
      (node (ref "U11") (pin "24") (pinfunction "DATA0_24") (pintype "bidirectional"))
    )
    (net (code "111") (name "unconnected-(U11-DATA1-Pad23)") (class "Default")
      (node (ref "U11") (pin "23") (pinfunction "DATA1_23") (pintype "bidirectional"))
    )
    (net (code "112") (name "unconnected-(U11-DATA2-Pad22)") (class "Default")
      (node (ref "U11") (pin "22") (pinfunction "DATA2_22") (pintype "bidirectional"))
    )
    (net (code "113") (name "unconnected-(U11-DATA3-Pad21)") (class "Default")
      (node (ref "U11") (pin "21") (pinfunction "DATA3_21") (pintype "bidirectional"))
    )
    (net (code "114") (name "unconnected-(U11-DATA4-Pad20)") (class "Default")
      (node (ref "U11") (pin "20") (pinfunction "DATA4_20") (pintype "bidirectional"))
    )
    (net (code "115") (name "unconnected-(U11-DATA5-Pad19)") (class "Default")
      (node (ref "U11") (pin "19") (pinfunction "DATA5_19") (pintype "bidirectional"))
    )
    (net (code "116") (name "unconnected-(U11-DATA6-Pad18)") (class "Default")
      (node (ref "U11") (pin "18") (pinfunction "DATA6_18") (pintype "bidirectional"))
    )
    (net (code "117") (name "unconnected-(U11-DATA7-Pad17)") (class "Default")
      (node (ref "U11") (pin "17") (pinfunction "DATA7_17") (pintype "bidirectional"))
    )
    (net (code "118") (name "unconnected-(U11-DIR-Pad12)") (class "Default")
      (node (ref "U11") (pin "12") (pinfunction "DIR_12") (pintype "output"))
    )
    (net (code "119") (name "unconnected-(U11-DM-Pad8)") (class "Default")
      (node (ref "U11") (pin "8") (pinfunction "DM_8") (pintype "bidirectional"))
    )
    (net (code "120") (name "unconnected-(U11-DP-Pad7)") (class "Default")
      (node (ref "U11") (pin "7") (pinfunction "DP_7") (pintype "bidirectional"))
    )
    (net (code "121") (name "unconnected-(U11-EPAD-Pad33)") (class "Default")
      (node (ref "U11") (pin "33") (pinfunction "EPAD_33") (pintype "passive"))
    )
    (net (code "122") (name "unconnected-(U11-EXTVBUS-Pad10)") (class "Default")
      (node (ref "U11") (pin "10") (pinfunction "EXTVBUS_10") (pintype "input"))
    )
    (net (code "123") (name "unconnected-(U11-GND-Pad1)") (class "Default")
      (node (ref "U11") (pin "1") (pinfunction "GND_1") (pintype "power_in"))
    )
    (net (code "124") (name "unconnected-(U11-GND-Pad2)") (class "Default")
      (node (ref "U11") (pin "2") (pinfunction "GND_2") (pintype "power_in"))
    )
    (net (code "125") (name "unconnected-(U11-ID-Pad5)") (class "Default")
      (node (ref "U11") (pin "5") (pinfunction "ID_5") (pintype "input"))
    )
    (net (code "126") (name "unconnected-(U11-NXT-Pad11)") (class "Default")
      (node (ref "U11") (pin "11") (pinfunction "NXT_11") (pintype "output"))
    )
    (net (code "127") (name "unconnected-(U11-RBIAS-Pad32)") (class "Default")
      (node (ref "U11") (pin "32") (pinfunction "RBIAS_32") (pintype "passive"))
    )
    (net (code "128") (name "unconnected-(U11-REG_EN-Pad31)") (class "Default")
      (node (ref "U11") (pin "31") (pinfunction "REG_EN_31") (pintype "bidirectional"))
    )
    (net (code "129") (name "unconnected-(U11-RESET-Pad9)") (class "Default")
      (node (ref "U11") (pin "9") (pinfunction "RESET_9") (pintype "input"))
    )
    (net (code "130") (name "unconnected-(U11-STP-Pad13)") (class "Default")
      (node (ref "U11") (pin "13") (pinfunction "STP_13") (pintype "input"))
    )
    (net (code "131") (name "unconnected-(U11-VBUS-Pad4)") (class "Default")
      (node (ref "U11") (pin "4") (pinfunction "VBUS_4") (pintype "bidirectional"))
    )
    (net (code "132") (name "unconnected-(U11-VDD1.8-Pad15)") (class "Default")
      (node (ref "U11") (pin "15") (pinfunction "VDD1.8_15") (pintype "power_in"))
    )
    (net (code "133") (name "unconnected-(U11-VDD1.8-Pad26)") (class "Default")
      (node (ref "U11") (pin "26") (pinfunction "VDD1.8_26") (pintype "power_in"))
    )
    (net (code "134") (name "unconnected-(U11-VDD3.3-Pad6)") (class "Default")
      (node (ref "U11") (pin "6") (pinfunction "VDD3.3_6") (pintype "power_in"))
    )
    (net (code "135") (name "unconnected-(U11-VDD3.3-Pad16)") (class "Default")
      (node (ref "U11") (pin "16") (pinfunction "VDD3.3_16") (pintype "power_in"))
    )
    (net (code "136") (name "unconnected-(U11-VDD3.3-Pad25)") (class "Default")
      (node (ref "U11") (pin "25") (pinfunction "VDD3.3_25") (pintype "power_in"))
    )
    (net (code "137") (name "unconnected-(U11-VDD3.3-Pad30)") (class "Default")
      (node (ref "U11") (pin "30") (pinfunction "VDD3.3_30") (pintype "power_in"))
    )
    (net (code "138") (name "unconnected-(U11-VDDA1.8-Pad29)") (class "Default")
      (node (ref "U11") (pin "29") (pinfunction "VDDA1.8_29") (pintype "power_in"))
    )
    (net (code "139") (name "unconnected-(U11-XI-Pad28)") (class "Default")
      (node (ref "U11") (pin "28") (pinfunction "XI_28") (pintype "input"))
    )
    (net (code "140") (name "unconnected-(U11-XO-Pad27)") (class "Default")
      (node (ref "U11") (pin "27") (pinfunction "XO_27") (pintype "output"))
    )
  )
)
